# control.net
KiCad netlist of a schematic drawn in Altium Designer
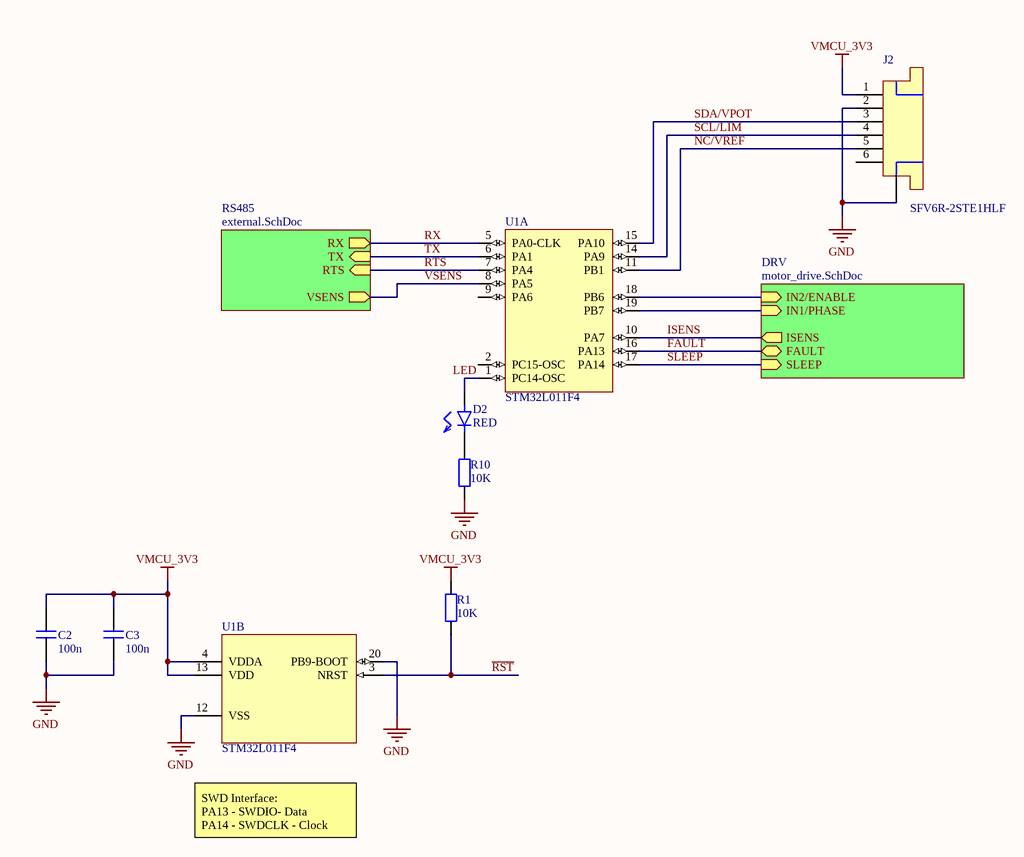
[diagram p0: control.SchDoc]

(export (version "E")
  (design (tool "Eeschema 10.0.6"))
  (components
    (comp (ref "C2")
      (value "100n")
      (footprint "CAPC1005X06N")
      (description "Capacitor")
      (fields (field (name "Comment") "cap"))
      (libsource (lib "lib_passives") (part "cap"))
    )
    (comp (ref "C3")
      (value "100n")
      (footprint "CAPC1005X06N")
      (description "Capacitor")
      (fields (field (name "Comment") "cap"))
      (libsource (lib "lib_passives") (part "cap"))
    )
    (comp (ref "D2")
      (value "RED")
      (footprint "CAPCP1005X06N")
      (description "LED")
      (fields (field (name "Comment") "led"))
      (libsource (lib "lib_actives") (part "led"))
    )
    (comp (ref "J2")
      (value "SFV6R-2STE1HLF")
      (footprint "SFV6R-2STE1HLF")
      (description "6 Position FFC, FPC Connector Contacts, Top 0.020\" (0.50mm) Surface Mount, Right Angle")
      (libsource (lib "lib_amphenol") (part "sfv6r-2ste1hlf"))
    )
    (comp (ref "R1")
      (value "10K")
      (footprint "RESC1005X04N")
      (description "Resistor")
      (fields (field (name "Comment") "res"))
      (libsource (lib "") (part "res_1"))
    )
    (comp (ref "R10")
      (value "10K")
      (footprint "RESC1005X04N")
      (description "Resistor")
      (fields (field (name "Comment") "res"))
      (libsource (lib "lib_passives") (part "res"))
    )
    (comp (ref "U1")
      (value "STM32L011F4")
      (footprint "QFN50P300X300X60-20N")
      (libsource (lib "") (part "stm32l011f4u_1"))
    )
  )
  (nets
    (net (code "1") (name "/FAULT") (class "Default")
      (node (ref "U1") (pin "16") (pinfunction "PA13_16") (pintype "bidirectional"))
    )
    (net (code "2") (name "/IN1{slash}PHASE") (class "Default")
      (node (ref "U1") (pin "19") (pinfunction "PB7_19") (pintype "bidirectional"))
    )
    (net (code "3") (name "/IN2{slash}ENABLE") (class "Default")
      (node (ref "U1") (pin "18") (pinfunction "PB6_18") (pintype "bidirectional"))
    )
    (net (code "4") (name "/ISENS") (class "Default")
      (node (ref "U1") (pin "10") (pinfunction "PA7_10") (pintype "bidirectional"))
    )
    (net (code "5") (name "/LED") (class "Default")
      (node (ref "D2") (pin "A") (pinfunction "A_A") (pintype "passive"))
      (node (ref "U1") (pin "1") (pinfunction "PC14-OSC_1") (pintype "bidirectional"))
    )
    (net (code "6") (name "/NC{slash}VREF") (class "Default")
      (node (ref "J2") (pin "5") (pinfunction "5_5") (pintype "passive"))
      (node (ref "U1") (pin "11") (pinfunction "PB1_11") (pintype "bidirectional"))
    )
    (net (code "7") (name "/RST") (class "Default")
      (node (ref "R1") (pin "1") (pinfunction "1_1") (pintype "passive"))
      (node (ref "U1") (pin "3") (pinfunction "NRST_3") (pintype "input"))
    )
    (net (code "8") (name "/RTS") (class "Default")
      (node (ref "U1") (pin "7") (pinfunction "PA4_7") (pintype "bidirectional"))
    )
    (net (code "9") (name "/RX") (class "Default")
      (node (ref "U1") (pin "5") (pinfunction "PA0-CLK_5") (pintype "bidirectional"))
    )
    (net (code "10") (name "/SCL{slash}LIM") (class "Default")
      (node (ref "J2") (pin "4") (pinfunction "4_4") (pintype "passive"))
      (node (ref "U1") (pin "14") (pinfunction "PA9_14") (pintype "bidirectional"))
    )
    (net (code "11") (name "/SDA{slash}VPOT") (class "Default")
      (node (ref "J2") (pin "3") (pinfunction "3_3") (pintype "passive"))
      (node (ref "U1") (pin "15") (pinfunction "PA10_15") (pintype "bidirectional"))
    )
    (net (code "12") (name "/SLEEP") (class "Default")
      (node (ref "U1") (pin "17") (pinfunction "PA14_17") (pintype "bidirectional"))
    )
    (net (code "13") (name "/TX") (class "Default")
      (node (ref "U1") (pin "6") (pinfunction "PA1_6") (pintype "bidirectional"))
    )
    (net (code "14") (name "/VSENS") (class "Default")
      (node (ref "U1") (pin "8") (pinfunction "PA5_8") (pintype "bidirectional"))
    )
    (net (code "15") (name "GND") (class "Default")
      (node (ref "C2") (pin "1") (pinfunction "1_1") (pintype "passive"))
      (node (ref "C3") (pin "1") (pinfunction "1_1") (pintype "passive"))
      (node (ref "J2") (pin "2") (pinfunction "2_2") (pintype "passive"))
      (node (ref "J2") (pin "ANCHOR") (pinfunction "7_ANCHOR") (pintype "passive"))
      (node (ref "R10") (pin "1") (pinfunction "1_1") (pintype "passive"))
      (node (ref "U1") (pin "12") (pinfunction "VSS_12") (pintype "power_in"))
      (node (ref "U1") (pin "20") (pinfunction "PB9-BOOT_20") (pintype "bidirectional"))
    )
    (net (code "16") (name "Net-(D2-PadC)") (class "Default")
      (node (ref "D2") (pin "C") (pinfunction "C_C") (pintype "passive"))
      (node (ref "R10") (pin "2") (pinfunction "2_2") (pintype "passive"))
    )
    (net (code "17") (name "VMCU_3V3") (class "Default")
      (node (ref "C2") (pin "2") (pinfunction "2_2") (pintype "passive"))
      (node (ref "C3") (pin "2") (pinfunction "2_2") (pintype "passive"))
      (node (ref "J2") (pin "1") (pinfunction "1_1") (pintype "passive"))
      (node (ref "R1") (pin "2") (pinfunction "2_2") (pintype "passive"))
      (node (ref "U1") (pin "13") (pinfunction "VDD_13") (pintype "power_in"))
      (node (ref "U1") (pin "4") (pinfunction "VDDA_4") (pintype "power_in"))
    )
    (net (code "18") (name "unconnected-(J2-Pad6)") (class "Default")
      (node (ref "J2") (pin "6") (pinfunction "6_6") (pintype "passive"))
    )
    (net (code "19") (name "unconnected-(U1A-PA6-Pad9)") (class "Default")
      (node (ref "U1") (pin "9") (pinfunction "PA6_9") (pintype "bidirectional"))
    )
    (net (code "20") (name "unconnected-(U1A-PC15-OSC-Pad2)") (class "Default")
      (node (ref "U1") (pin "2") (pinfunction "PC15-OSC_2") (pintype "bidirectional"))
    )
  )
)
